# USV-BG-002-SP-A.net
KiCad netlist of a schematic drawn in EAGLE
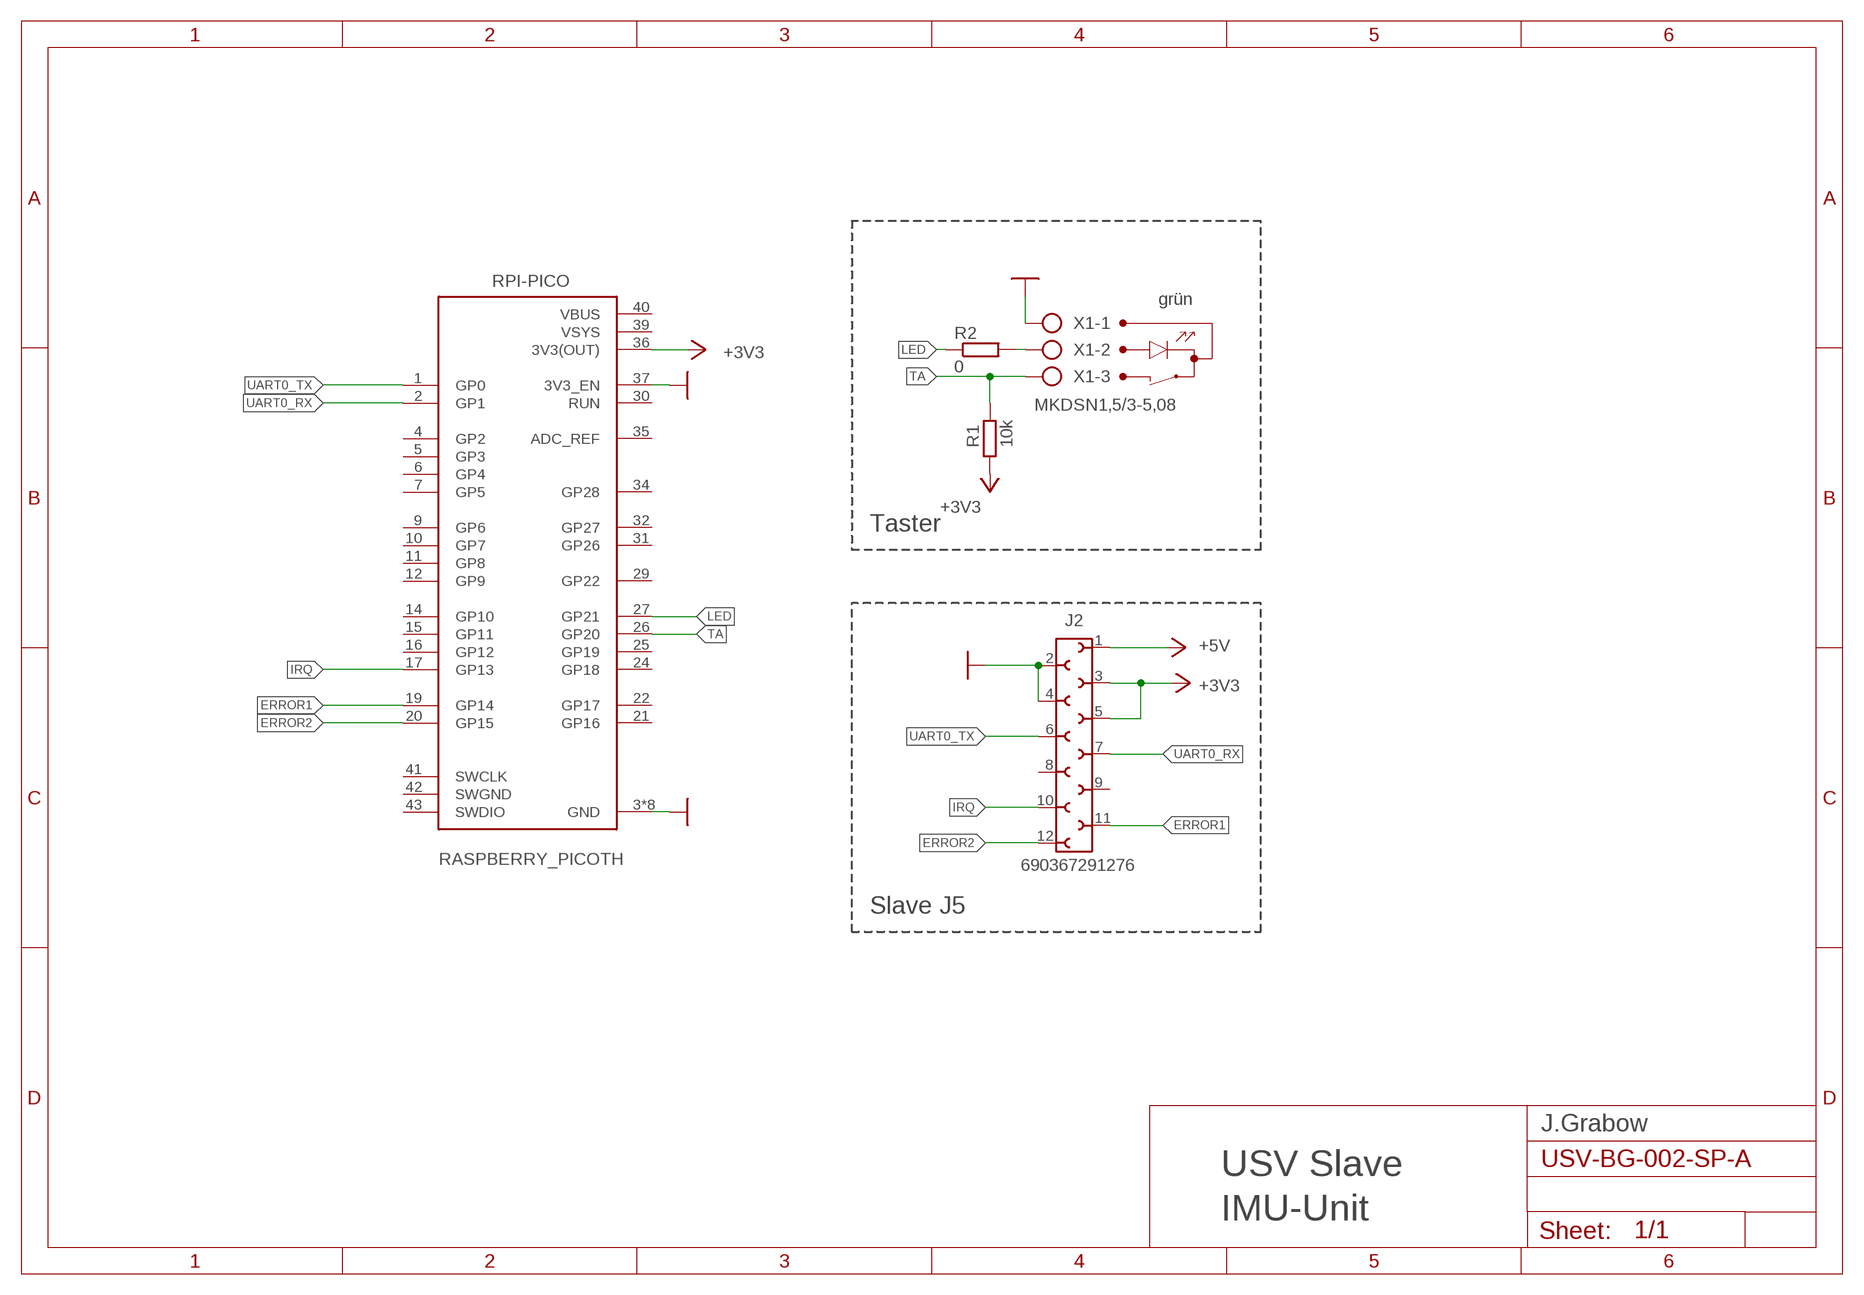
[diagram p0: schematic, sheet 1]

(export (version "E")
  (design (tool "Eeschema 10.0.6"))
  (components
    (comp (ref "J2")
      (value "690367291276")
      (footprint "eagle-import:690367291276")
      (libsource (lib "eagle-import") (part "690367291276"))
    )
    (comp (ref "R1")
      (value "10k")
      (footprint "eagle-import:M0805")
      (libsource (lib "eagle-import") (part "R-EU_M0805"))
    )
    (comp (ref "R2")
      (value "0")
      (footprint "eagle-import:R0805")
      (libsource (lib "eagle-import") (part "R-EU_R0805"))
    )
    (comp (ref "RPI-PICO")
      (value "RASPBERRY_PICOTH")
      (footprint "eagle-import:PICO-PKG-TH")
      (libsource (lib "eagle-import") (part "RASPBERRY_PICOTH"))
    )
    (comp (ref "X1")
      (value "MKDSN1,5/3-5,08")
      (footprint "eagle-import:MKDSN1,5_3-5,08")
      (libsource (lib "eagle-import") (part "MKDSN1,5/3-5,08"))
    )
  )
  (nets
    (net (code "1") (name "+3V3") (class "Default")
      (node (ref "J2") (pin "3") (pinfunction "3_3") (pintype "passive"))
      (node (ref "J2") (pin "5") (pinfunction "5_5") (pintype "passive"))
      (node (ref "R1") (pin "1") (pinfunction "1_1") (pintype "passive"))
      (node (ref "RPI-PICO") (pin "36") (pinfunction "3V3(OUT)_36") (pintype "power_in"))
    )
    (net (code "2") (name "+5V") (class "Default")
      (node (ref "J2") (pin "1") (pinfunction "1_1") (pintype "passive"))
    )
    (net (code "3") (name "/SWGND") (class "Default")
      (node (ref "RPI-PICO") (pin "42") (pinfunction "SWGND_42") (pintype "power_in"))
    )
    (net (code "4") (name "/VBUS") (class "Default")
      (node (ref "RPI-PICO") (pin "40") (pinfunction "VBUS_40") (pintype "power_in"))
    )
    (net (code "5") (name "/VSYS") (class "Default")
      (node (ref "RPI-PICO") (pin "39") (pinfunction "VSYS_39") (pintype "power_in"))
    )
    (net (code "6") (name "ERROR1") (class "Default")
      (node (ref "J2") (pin "11") (pinfunction "11_11") (pintype "passive"))
      (node (ref "RPI-PICO") (pin "19") (pinfunction "GP14_19") (pintype "bidirectional"))
    )
    (net (code "7") (name "ERROR2") (class "Default")
      (node (ref "J2") (pin "12") (pinfunction "12_12") (pintype "passive"))
      (node (ref "RPI-PICO") (pin "20") (pinfunction "GP15_20") (pintype "bidirectional"))
    )
    (net (code "8") (name "GND") (class "Default")
      (node (ref "J2") (pin "2") (pinfunction "2_2") (pintype "passive"))
      (node (ref "J2") (pin "4") (pinfunction "4_4") (pintype "passive"))
      (node (ref "RPI-PICO") (pin "13") (pinfunction "GND_13") (pintype "power_in"))
      (node (ref "RPI-PICO") (pin "18") (pinfunction "GND_18") (pintype "power_in"))
      (node (ref "RPI-PICO") (pin "23") (pinfunction "GND_23") (pintype "power_in"))
      (node (ref "RPI-PICO") (pin "28") (pinfunction "GND_28") (pintype "power_in"))
      (node (ref "RPI-PICO") (pin "3") (pinfunction "GND_3") (pintype "power_in"))
      (node (ref "RPI-PICO") (pin "33") (pinfunction "GND_33") (pintype "power_in"))
      (node (ref "RPI-PICO") (pin "37") (pinfunction "3V3_EN_37") (pintype "input"))
      (node (ref "RPI-PICO") (pin "38") (pinfunction "GND_38") (pintype "power_in"))
      (node (ref "RPI-PICO") (pin "8") (pinfunction "GND_8") (pintype "power_in"))
      (node (ref "X1") (pin "1") (pinfunction "KL_1") (pintype "passive"))
    )
    (net (code "9") (name "IRQ") (class "Default")
      (node (ref "J2") (pin "10") (pinfunction "10_10") (pintype "passive"))
      (node (ref "RPI-PICO") (pin "17") (pinfunction "GP13_17") (pintype "bidirectional"))
    )
    (net (code "10") (name "LED") (class "Default")
      (node (ref "R2") (pin "1") (pinfunction "1_1") (pintype "passive"))
      (node (ref "RPI-PICO") (pin "27") (pinfunction "GP21_27") (pintype "bidirectional"))
    )
    (net (code "11") (name "Net-(X1B-KL)") (class "Default")
      (node (ref "R2") (pin "2") (pinfunction "2_2") (pintype "passive"))
      (node (ref "X1") (pin "2") (pinfunction "KL_2") (pintype "passive"))
    )
    (net (code "12") (name "TA") (class "Default")
      (node (ref "R1") (pin "2") (pinfunction "2_2") (pintype "passive"))
      (node (ref "RPI-PICO") (pin "26") (pinfunction "GP20_26") (pintype "bidirectional"))
      (node (ref "X1") (pin "3") (pinfunction "KL_3") (pintype "passive"))
    )
    (net (code "13") (name "UART0_RX") (class "Default")
      (node (ref "J2") (pin "7") (pinfunction "7_7") (pintype "passive"))
      (node (ref "RPI-PICO") (pin "2") (pinfunction "GP1_2") (pintype "bidirectional"))
    )
    (net (code "14") (name "UART0_TX") (class "Default")
      (node (ref "J2") (pin "6") (pinfunction "6_6") (pintype "passive"))
      (node (ref "RPI-PICO") (pin "1") (pinfunction "GP0_1") (pintype "bidirectional"))
    )
    (net (code "15") (name "unconnected-(J2-Pad8)") (class "Default")
      (node (ref "J2") (pin "8") (pinfunction "8_8") (pintype "passive"))
    )
    (net (code "16") (name "unconnected-(J2-Pad9)") (class "Default")
      (node (ref "J2") (pin "9") (pinfunction "9_9") (pintype "passive"))
    )
    (net (code "17") (name "unconnected-(RPI-PICO-ADC_REF-Pad35)") (class "Default")
      (node (ref "RPI-PICO") (pin "35") (pinfunction "ADC_REF_35") (pintype "input"))
    )
    (net (code "18") (name "unconnected-(RPI-PICO-GP2-Pad4)") (class "Default")
      (node (ref "RPI-PICO") (pin "4") (pinfunction "GP2_4") (pintype "bidirectional"))
    )
    (net (code "19") (name "unconnected-(RPI-PICO-GP3-Pad5)") (class "Default")
      (node (ref "RPI-PICO") (pin "5") (pinfunction "GP3_5") (pintype "bidirectional"))
    )
    (net (code "20") (name "unconnected-(RPI-PICO-GP4-Pad6)") (class "Default")
      (node (ref "RPI-PICO") (pin "6") (pinfunction "GP4_6") (pintype "bidirectional"))
    )
    (net (code "21") (name "unconnected-(RPI-PICO-GP5-Pad7)") (class "Default")
      (node (ref "RPI-PICO") (pin "7") (pinfunction "GP5_7") (pintype "bidirectional"))
    )
    (net (code "22") (name "unconnected-(RPI-PICO-GP6-Pad9)") (class "Default")
      (node (ref "RPI-PICO") (pin "9") (pinfunction "GP6_9") (pintype "bidirectional"))
    )
    (net (code "23") (name "unconnected-(RPI-PICO-GP7-Pad10)") (class "Default")
      (node (ref "RPI-PICO") (pin "10") (pinfunction "GP7_10") (pintype "bidirectional"))
    )
    (net (code "24") (name "unconnected-(RPI-PICO-GP8-Pad11)") (class "Default")
      (node (ref "RPI-PICO") (pin "11") (pinfunction "GP8_11") (pintype "bidirectional"))
    )
    (net (code "25") (name "unconnected-(RPI-PICO-GP9-Pad12)") (class "Default")
      (node (ref "RPI-PICO") (pin "12") (pinfunction "GP9_12") (pintype "bidirectional"))
    )
    (net (code "26") (name "unconnected-(RPI-PICO-GP10-Pad14)") (class "Default")
      (node (ref "RPI-PICO") (pin "14") (pinfunction "GP10_14") (pintype "bidirectional"))
    )
    (net (code "27") (name "unconnected-(RPI-PICO-GP11-Pad15)") (class "Default")
      (node (ref "RPI-PICO") (pin "15") (pinfunction "GP11_15") (pintype "bidirectional"))
    )
    (net (code "28") (name "unconnected-(RPI-PICO-GP12-Pad16)") (class "Default")
      (node (ref "RPI-PICO") (pin "16") (pinfunction "GP12_16") (pintype "bidirectional"))
    )
    (net (code "29") (name "unconnected-(RPI-PICO-GP16-Pad21)") (class "Default")
      (node (ref "RPI-PICO") (pin "21") (pinfunction "GP16_21") (pintype "bidirectional"))
    )
    (net (code "30") (name "unconnected-(RPI-PICO-GP17-Pad22)") (class "Default")
      (node (ref "RPI-PICO") (pin "22") (pinfunction "GP17_22") (pintype "bidirectional"))
    )
    (net (code "31") (name "unconnected-(RPI-PICO-GP18-Pad24)") (class "Default")
      (node (ref "RPI-PICO") (pin "24") (pinfunction "GP18_24") (pintype "bidirectional"))
    )
    (net (code "32") (name "unconnected-(RPI-PICO-GP19-Pad25)") (class "Default")
      (node (ref "RPI-PICO") (pin "25") (pinfunction "GP19_25") (pintype "bidirectional"))
    )
    (net (code "33") (name "unconnected-(RPI-PICO-GP22-Pad29)") (class "Default")
      (node (ref "RPI-PICO") (pin "29") (pinfunction "GP22_29") (pintype "bidirectional"))
    )
    (net (code "34") (name "unconnected-(RPI-PICO-GP26-Pad31)") (class "Default")
      (node (ref "RPI-PICO") (pin "31") (pinfunction "GP26_31") (pintype "bidirectional"))
    )
    (net (code "35") (name "unconnected-(RPI-PICO-GP27-Pad32)") (class "Default")
      (node (ref "RPI-PICO") (pin "32") (pinfunction "GP27_32") (pintype "bidirectional"))
    )
    (net (code "36") (name "unconnected-(RPI-PICO-GP28-Pad34)") (class "Default")
      (node (ref "RPI-PICO") (pin "34") (pinfunction "GP28_34") (pintype "bidirectional"))
    )
    (net (code "37") (name "unconnected-(RPI-PICO-RUN-Pad30)") (class "Default")
      (node (ref "RPI-PICO") (pin "30") (pinfunction "RUN_30") (pintype "input"))
    )
    (net (code "38") (name "unconnected-(RPI-PICO-SWCLK-Pad41)") (class "Default")
      (node (ref "RPI-PICO") (pin "41") (pinfunction "SWCLK_41") (pintype "input"))
    )
    (net (code "39") (name "unconnected-(RPI-PICO-SWDIO-Pad43)") (class "Default")
      (node (ref "RPI-PICO") (pin "43") (pinfunction "SWDIO_43") (pintype "bidirectional"))
    )
  )
)
